# what-the-frequency-mk-5.net
KiCad netlist of a schematic drawn in EAGLE
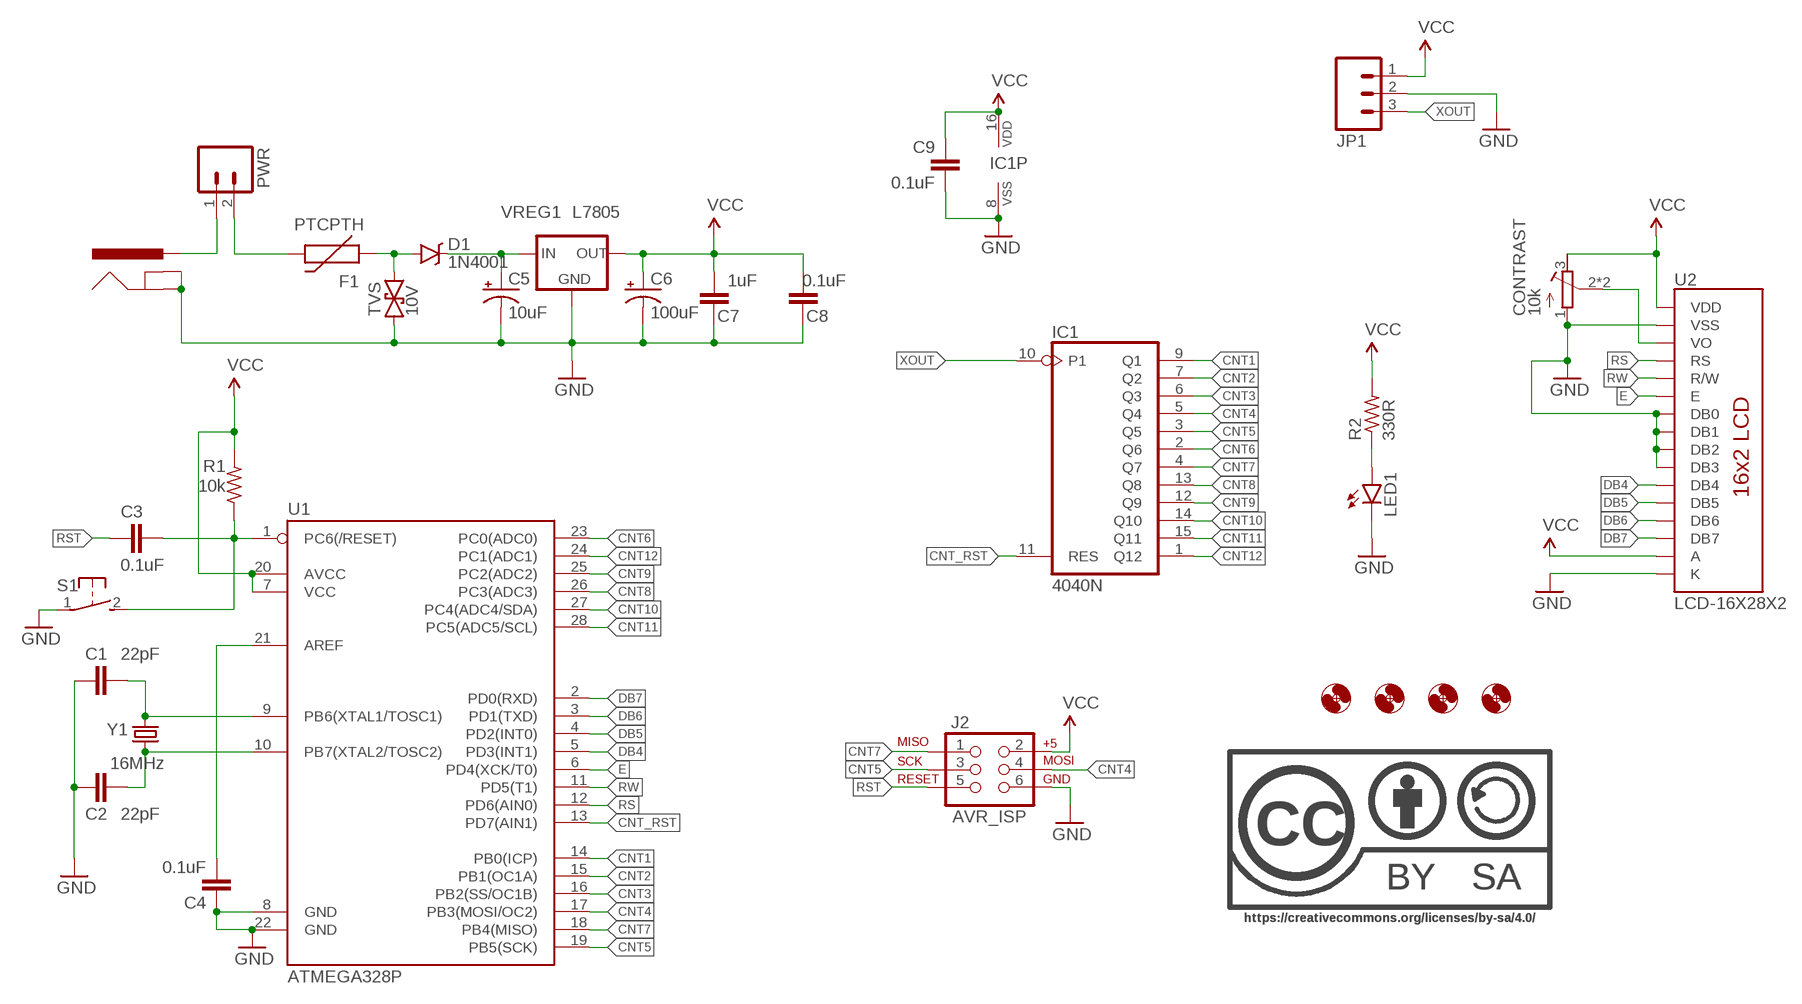
[diagram p0: schematic, sheet 1]

(export (version "E")
  (design (tool "Eeschema 10.0.6"))
  (components
    (comp (ref "C1")
      (value "22pF")
      (footprint "eagle-import:C025-024X044")
      (libsource (lib "eagle-import") (part "CAPACITOR-CERAMIC025-024X044"))
    )
    (comp (ref "C2")
      (value "22pF")
      (footprint "eagle-import:C025-024X044")
      (libsource (lib "eagle-import") (part "CAPACITOR-CERAMIC025-024X044"))
    )
    (comp (ref "C3")
      (value "0.1uF")
      (footprint "eagle-import:C025-024X044")
      (libsource (lib "eagle-import") (part "CAPACITOR-CERAMIC025-024X044"))
    )
    (comp (ref "C4")
      (value "0.1uF")
      (footprint "eagle-import:C025-024X044")
      (libsource (lib "eagle-import") (part "CAPACITOR-CERAMIC025-024X044"))
    )
    (comp (ref "C5")
      (value "10uF")
      (footprint "eagle-import:E2-5")
      (libsource (lib "eagle-import") (part "CAPACITOR-POLARIZEDE2-5"))
    )
    (comp (ref "C6")
      (value "100uF")
      (footprint "eagle-import:E2,5-6")
      (libsource (lib "eagle-import") (part "CAPACITOR-POLARIZEDE2.5-6"))
    )
    (comp (ref "C7")
      (value "1uF")
      (footprint "eagle-import:C025-024X044")
      (libsource (lib "eagle-import") (part "CAPACITOR-CERAMIC025-024X044"))
    )
    (comp (ref "C8")
      (value "0.1uF")
      (footprint "eagle-import:C025-024X044")
      (libsource (lib "eagle-import") (part "CAPACITOR-CERAMIC025-024X044"))
    )
    (comp (ref "C9")
      (value "0.1uF")
      (footprint "eagle-import:C025-024X044")
      (libsource (lib "eagle-import") (part "CAPACITOR-CERAMIC025-024X044"))
    )
    (comp (ref "CONTRAST")
      (value "10k")
      (footprint "eagle-import:POT-THUMBWHEEL")
      (libsource (lib "eagle-import") (part "POTENTIOMETERTHUMBWHEEL-16MM"))
    )
    (comp (ref "D1")
      (value "1N4001")
      (footprint "eagle-import:DO-41")
      (libsource (lib "eagle-import") (part "DIODE-SCHOTTKYDO-41"))
    )
    (comp (ref "F1")
      (value "PTCPTH")
      (footprint "eagle-import:PTC")
      (libsource (lib "eagle-import") (part "PTCPTH"))
    )
    (comp (ref "H1")
      (value "HOLE#4")
      (footprint "eagle-import:HOLE-#4")
      (libsource (lib "eagle-import") (part "HOLE#4"))
    )
    (comp (ref "H2")
      (value "HOLE#4")
      (footprint "eagle-import:HOLE-#4")
      (libsource (lib "eagle-import") (part "HOLE#4"))
    )
    (comp (ref "H3")
      (value "HOLE#4")
      (footprint "eagle-import:HOLE-#4")
      (libsource (lib "eagle-import") (part "HOLE#4"))
    )
    (comp (ref "H4")
      (value "HOLE#4")
      (footprint "eagle-import:HOLE-#4")
      (libsource (lib "eagle-import") (part "HOLE#4"))
    )
    (comp (ref "IC1")
      (value "4040N")
      (footprint "eagle-import:DIL16")
      (libsource (lib "eagle-import") (part "4040N"))
    )
    (comp (ref "J1")
      (value "POWER_JACKPTH")
      (footprint "eagle-import:POWER_JACK_PTH")
      (libsource (lib "eagle-import") (part "POWER_JACKPTH"))
    )
    (comp (ref "J2")
      (value "AVR_ISP")
      (footprint "eagle-import:AVR_MINI_PROG")
      (libsource (lib "eagle-import") (part "AVR_SPI_PRG_6INLINE"))
    )
    (comp (ref "JP1")
      (value "M03PTH")
      (footprint "eagle-import:1X03")
      (libsource (lib "eagle-import") (part "M03PTH"))
    )
    (comp (ref "LED1")
      (value "LED3MM")
      (footprint "eagle-import:LED3MM")
      (libsource (lib "eagle-import") (part "LED3MM"))
    )
    (comp (ref "PWR")
      (value "M02PTH")
      (footprint "eagle-import:1X02")
      (libsource (lib "eagle-import") (part "M02PTH"))
    )
    (comp (ref "R1")
      (value "10k")
      (footprint "eagle-import:RESISTOR-AXIAL-PTH-7.68MM")
      (libsource (lib "eagle-import") (part "RESISTORPTH-AXIAL-7.68MM"))
    )
    (comp (ref "R2")
      (value "330R")
      (footprint "eagle-import:RESISTOR-AXIAL-PTH-6.35MM")
      (libsource (lib "eagle-import") (part "RESISTORPTH-AXIAL-6.35MM"))
    )
    (comp (ref "S1")
      (value "DTS-3")
      (footprint "eagle-import:DTS-3")
      (libsource (lib "eagle-import") (part "DTS-3"))
    )
    (comp (ref "TVS")
      (value "10V")
      (footprint "eagle-import:DO-41-TVS")
      (libsource (lib "eagle-import") (part "TVSDO-41-TVS-BIDIRECTIONAL"))
    )
    (comp (ref "U$3")
      (value "CC-BY-SA-4.0NO-URL")
      (footprint "eagle-import:CC-BY-SA-4.0-NO-URL")
      (libsource (lib "eagle-import") (part "CC-BY-SA-4.0NO-URL"))
    )
    (comp (ref "U$7")
      (value "CC-BY-SA-4.0NO-URL")
      (footprint "eagle-import:CC-BY-SA-4.0-NO-URL")
      (libsource (lib "eagle-import") (part "CC-BY-SA-4.0NO-URL"))
    )
    (comp (ref "U1")
      (value "ATMEGA328P")
      (footprint "eagle-import:DIL28-3")
      (libsource (lib "eagle-import") (part "ATMEGA328P_PDIP"))
    )
    (comp (ref "U2")
      (value "LCD-16X28X2")
      (footprint "eagle-import:LCD-8X2")
      (libsource (lib "eagle-import") (part "LCD-16X28X2"))
    )
    (comp (ref "VREG1")
      (value "L7805")
      (footprint "eagle-import:TO220V")
      (libsource (lib "eagle-import") (part "V_REG_78XXTO-220-IGO-VERT"))
    )
    (comp (ref "Y1")
      (value "16MHz")
      (footprint "eagle-import:HC49U-V")
      (libsource (lib "eagle-import") (part "CRYSTALHC49UV"))
    )
  )
  (nets
    (net (code "1") (name "CNT1") (class "Default")
      (node (ref "IC1") (pin "9") (pinfunction "Q1_9") (pintype "output"))
      (node (ref "U1") (pin "14") (pinfunction "PB0(ICP)_14") (pintype "bidirectional"))
    )
    (net (code "2") (name "CNT2") (class "Default")
      (node (ref "IC1") (pin "7") (pinfunction "Q2_7") (pintype "output"))
      (node (ref "U1") (pin "15") (pinfunction "PB1(OC1A)_15") (pintype "bidirectional"))
    )
    (net (code "3") (name "CNT3") (class "Default")
      (node (ref "IC1") (pin "6") (pinfunction "Q3_6") (pintype "output"))
      (node (ref "U1") (pin "16") (pinfunction "PB2(SS/OC1B)_16") (pintype "bidirectional"))
    )
    (net (code "4") (name "CNT4") (class "Default")
      (node (ref "IC1") (pin "5") (pinfunction "Q4_5") (pintype "output"))
      (node (ref "J2") (pin "4") (pinfunction "4_4") (pintype "passive"))
      (node (ref "U1") (pin "17") (pinfunction "PB3(MOSI/OC2)_17") (pintype "bidirectional"))
    )
    (net (code "5") (name "CNT5") (class "Default")
      (node (ref "IC1") (pin "3") (pinfunction "Q5_3") (pintype "output"))
      (node (ref "J2") (pin "3") (pinfunction "3_3") (pintype "passive"))
      (node (ref "U1") (pin "19") (pinfunction "PB5(SCK)_19") (pintype "bidirectional"))
    )
    (net (code "6") (name "CNT6") (class "Default")
      (node (ref "IC1") (pin "2") (pinfunction "Q6_2") (pintype "output"))
      (node (ref "U1") (pin "23") (pinfunction "PC0(ADC0)_23") (pintype "bidirectional"))
    )
    (net (code "7") (name "CNT7") (class "Default")
      (node (ref "IC1") (pin "4") (pinfunction "Q7_4") (pintype "output"))
      (node (ref "J2") (pin "1") (pinfunction "1_1") (pintype "passive"))
      (node (ref "U1") (pin "18") (pinfunction "PB4(MISO)_18") (pintype "bidirectional"))
    )
    (net (code "8") (name "CNT8") (class "Default")
      (node (ref "IC1") (pin "13") (pinfunction "Q8_13") (pintype "output"))
      (node (ref "U1") (pin "26") (pinfunction "PC3(ADC3)_26") (pintype "bidirectional"))
    )
    (net (code "9") (name "CNT9") (class "Default")
      (node (ref "IC1") (pin "12") (pinfunction "Q9_12") (pintype "output"))
      (node (ref "U1") (pin "25") (pinfunction "PC2(ADC2)_25") (pintype "bidirectional"))
    )
    (net (code "10") (name "CNT10") (class "Default")
      (node (ref "IC1") (pin "14") (pinfunction "Q10_14") (pintype "output"))
      (node (ref "U1") (pin "27") (pinfunction "PC4(ADC4/SDA)_27") (pintype "bidirectional"))
    )
    (net (code "11") (name "CNT11") (class "Default")
      (node (ref "IC1") (pin "15") (pinfunction "Q11_15") (pintype "output"))
      (node (ref "U1") (pin "28") (pinfunction "PC5(ADC5/SCL)_28") (pintype "bidirectional"))
    )
    (net (code "12") (name "CNT12") (class "Default")
      (node (ref "IC1") (pin "1") (pinfunction "Q12_1") (pintype "output"))
      (node (ref "U1") (pin "24") (pinfunction "PC1(ADC1)_24") (pintype "bidirectional"))
    )
    (net (code "13") (name "CNT_RST") (class "Default")
      (node (ref "IC1") (pin "11") (pinfunction "RES_11") (pintype "input"))
      (node (ref "U1") (pin "13") (pinfunction "PD7(AIN1)_13") (pintype "bidirectional"))
    )
    (net (code "14") (name "DB4") (class "Default")
      (node (ref "U1") (pin "5") (pinfunction "PD3(INT1)_5") (pintype "bidirectional"))
      (node (ref "U2") (pin "11") (pinfunction "DB4_11") (pintype "bidirectional"))
    )
    (net (code "15") (name "DB5") (class "Default")
      (node (ref "U1") (pin "4") (pinfunction "PD2(INT0)_4") (pintype "bidirectional"))
      (node (ref "U2") (pin "12") (pinfunction "DB5_12") (pintype "bidirectional"))
    )
    (net (code "16") (name "DB6") (class "Default")
      (node (ref "U1") (pin "3") (pinfunction "PD1(TXD)_3") (pintype "bidirectional"))
      (node (ref "U2") (pin "13") (pinfunction "DB6_13") (pintype "bidirectional"))
    )
    (net (code "17") (name "DB7") (class "Default")
      (node (ref "U1") (pin "2") (pinfunction "PD0(RXD)_2") (pintype "bidirectional"))
      (node (ref "U2") (pin "14") (pinfunction "DB7_14") (pintype "bidirectional"))
    )
    (net (code "18") (name "E") (class "Default")
      (node (ref "U1") (pin "6") (pinfunction "PD4(XCK/T0)_6") (pintype "bidirectional"))
      (node (ref "U2") (pin "6") (pinfunction "E_6") (pintype "input"))
    )
    (net (code "19") (name "GND") (class "Default")
      (node (ref "C1") (pin "2") (pinfunction "2_2") (pintype "passive"))
      (node (ref "C2") (pin "2") (pinfunction "2_2") (pintype "passive"))
      (node (ref "C4") (pin "1") (pinfunction "1_1") (pintype "passive"))
      (node (ref "C5") (pin "-") (pinfunction "-_-") (pintype "passive"))
      (node (ref "C6") (pin "-") (pinfunction "-_-") (pintype "passive"))
      (node (ref "C7") (pin "1") (pinfunction "1_1") (pintype "passive"))
      (node (ref "C8") (pin "1") (pinfunction "1_1") (pintype "passive"))
      (node (ref "C9") (pin "1") (pinfunction "1_1") (pintype "passive"))
      (node (ref "CONTRAST") (pin "1") (pinfunction "A_1") (pintype "passive"))
      (node (ref "IC1") (pin "8") (pinfunction "VSS_8") (pintype "power_in"))
      (node (ref "J1") (pin "GND") (pinfunction "GND_GND") (pintype "bidirectional"))
      (node (ref "J1") (pin "GNDBREAK") (pinfunction "GNDBREAK_GNDBREAK") (pintype "bidirectional"))
      (node (ref "J2") (pin "6") (pinfunction "6_6") (pintype "passive"))
      (node (ref "JP1") (pin "2") (pinfunction "2_2") (pintype "passive"))
      (node (ref "LED1") (pin "K") (pinfunction "C_K") (pintype "passive"))
      (node (ref "S1") (pin "1") (pinfunction "1_1") (pintype "passive"))
      (node (ref "TVS") (pin "P$1") (pinfunction "1_P$1") (pintype "passive"))
      (node (ref "U1") (pin "22") (pinfunction "GND_22") (pintype "bidirectional"))
      (node (ref "U1") (pin "8") (pinfunction "GND_8") (pintype "bidirectional"))
      (node (ref "U2") (pin "1") (pinfunction "VSS_1") (pintype "power_in"))
      (node (ref "U2") (pin "10") (pinfunction "DB3_10") (pintype "bidirectional"))
      (node (ref "U2") (pin "16") (pinfunction "K_16") (pintype "power_in"))
      (node (ref "U2") (pin "7") (pinfunction "DB0_7") (pintype "bidirectional"))
      (node (ref "U2") (pin "8") (pinfunction "DB1_8") (pintype "bidirectional"))
      (node (ref "U2") (pin "9") (pinfunction "DB2_9") (pintype "bidirectional"))
      (node (ref "VREG1") (pin "2") (pinfunction "GND_2") (pintype "input"))
    )
    (net (code "20") (name "Net-(F1-1)") (class "Default")
      (node (ref "D1") (pin "A") (pinfunction "A_A") (pintype "passive"))
      (node (ref "F1") (pin "P$1") (pinfunction "1_P$1") (pintype "bidirectional"))
      (node (ref "TVS") (pin "P$2") (pinfunction "2_P$2") (pintype "passive"))
    )
    (net (code "21") (name "Net-(F1-2)") (class "Default")
      (node (ref "F1") (pin "P$2") (pinfunction "2_P$2") (pintype "bidirectional"))
      (node (ref "PWR") (pin "2") (pinfunction "2_2") (pintype "passive"))
    )
    (net (code "22") (name "Net-(J1-PadPWR)") (class "Default")
      (node (ref "J1") (pin "PWR") (pinfunction "PWR_PWR") (pintype "bidirectional"))
      (node (ref "PWR") (pin "1") (pinfunction "1_1") (pintype "passive"))
    )
    (net (code "23") (name "Net-(R1-1)") (class "Default")
      (node (ref "C3") (pin "2") (pinfunction "2_2") (pintype "passive"))
      (node (ref "R1") (pin "P$1") (pinfunction "1_P$1") (pintype "passive"))
      (node (ref "S1") (pin "2") (pinfunction "2_2") (pintype "passive"))
      (node (ref "U1") (pin "1") (pinfunction "PC6(/RESET)_1") (pintype "bidirectional"))
    )
    (net (code "24") (name "Net-(R2-1)") (class "Default")
      (node (ref "LED1") (pin "A") (pinfunction "A_A") (pintype "passive"))
      (node (ref "R2") (pin "P$1") (pinfunction "1_P$1") (pintype "passive"))
    )
    (net (code "25") (name "Net-(U1-AREF)") (class "Default")
      (node (ref "C4") (pin "2") (pinfunction "2_2") (pintype "passive"))
      (node (ref "U1") (pin "21") (pinfunction "AREF_21") (pintype "bidirectional"))
    )
    (net (code "26") (name "Net-(U1-PB6(XTAL1{slash}TOSC1))") (class "Default")
      (node (ref "C1") (pin "1") (pinfunction "1_1") (pintype "passive"))
      (node (ref "U1") (pin "9") (pinfunction "PB6(XTAL1/TOSC1)_9") (pintype "bidirectional"))
      (node (ref "Y1") (pin "2") (pinfunction "2_2") (pintype "passive"))
    )
    (net (code "27") (name "Net-(U1-PB7(XTAL2{slash}TOSC2))") (class "Default")
      (node (ref "C2") (pin "1") (pinfunction "1_1") (pintype "passive"))
      (node (ref "U1") (pin "10") (pinfunction "PB7(XTAL2/TOSC2)_10") (pintype "bidirectional"))
      (node (ref "Y1") (pin "1") (pinfunction "1_1") (pintype "passive"))
    )
    (net (code "28") (name "Net-(U2-VO)") (class "Default")
      (node (ref "CONTRAST") (pin "2") (pinfunction "S_2") (pintype "passive"))
      (node (ref "CONTRAST") (pin "2@1") (pinfunction "S_2@1") (pintype "passive"))
      (node (ref "U2") (pin "3") (pinfunction "VO_3") (pintype "bidirectional"))
    )
    (net (code "29") (name "Net-(VREG1-IN)") (class "Default")
      (node (ref "C5") (pin "+") (pinfunction "+_+") (pintype "passive"))
      (node (ref "D1") (pin "C") (pinfunction "C_C") (pintype "passive"))
      (node (ref "VREG1") (pin "1") (pinfunction "IN_1") (pintype "input"))
    )
    (net (code "30") (name "RS") (class "Default")
      (node (ref "U1") (pin "12") (pinfunction "PD6(AIN0)_12") (pintype "bidirectional"))
      (node (ref "U2") (pin "4") (pinfunction "RS_4") (pintype "input"))
    )
    (net (code "31") (name "RST") (class "Default")
      (node (ref "C3") (pin "1") (pinfunction "1_1") (pintype "passive"))
      (node (ref "J2") (pin "5") (pinfunction "5_5") (pintype "passive"))
    )
    (net (code "32") (name "RW") (class "Default")
      (node (ref "U1") (pin "11") (pinfunction "PD5(T1)_11") (pintype "bidirectional"))
      (node (ref "U2") (pin "5") (pinfunction "R/W_5") (pintype "input"))
    )
    (net (code "33") (name "VCC") (class "Default")
      (node (ref "C6") (pin "+") (pinfunction "+_+") (pintype "passive"))
      (node (ref "C7") (pin "2") (pinfunction "2_2") (pintype "passive"))
      (node (ref "C8") (pin "2") (pinfunction "2_2") (pintype "passive"))
      (node (ref "C9") (pin "2") (pinfunction "2_2") (pintype "passive"))
      (node (ref "CONTRAST") (pin "3") (pinfunction "E_3") (pintype "passive"))
      (node (ref "IC1") (pin "16") (pinfunction "VDD_16") (pintype "power_in"))
      (node (ref "J2") (pin "2") (pinfunction "2_2") (pintype "passive"))
      (node (ref "JP1") (pin "1") (pinfunction "1_1") (pintype "passive"))
      (node (ref "R1") (pin "P$2") (pinfunction "2_P$2") (pintype "passive"))
      (node (ref "R2") (pin "P$2") (pinfunction "2_P$2") (pintype "passive"))
      (node (ref "U1") (pin "20") (pinfunction "AVCC_20") (pintype "bidirectional"))
      (node (ref "U1") (pin "7") (pinfunction "VCC_7") (pintype "bidirectional"))
      (node (ref "U2") (pin "15") (pinfunction "A_15") (pintype "power_in"))
      (node (ref "U2") (pin "2") (pinfunction "VDD_2") (pintype "power_in"))
      (node (ref "VREG1") (pin "3") (pinfunction "OUT_3") (pintype "output"))
    )
    (net (code "34") (name "XOUT") (class "Default")
      (node (ref "IC1") (pin "10") (pinfunction "P1_10") (pintype "input"))
      (node (ref "JP1") (pin "3") (pinfunction "3_3") (pintype "passive"))
    )
  )
)
